# Sequei_board1.net
KiCad netlist of a schematic drawn in EAGLE
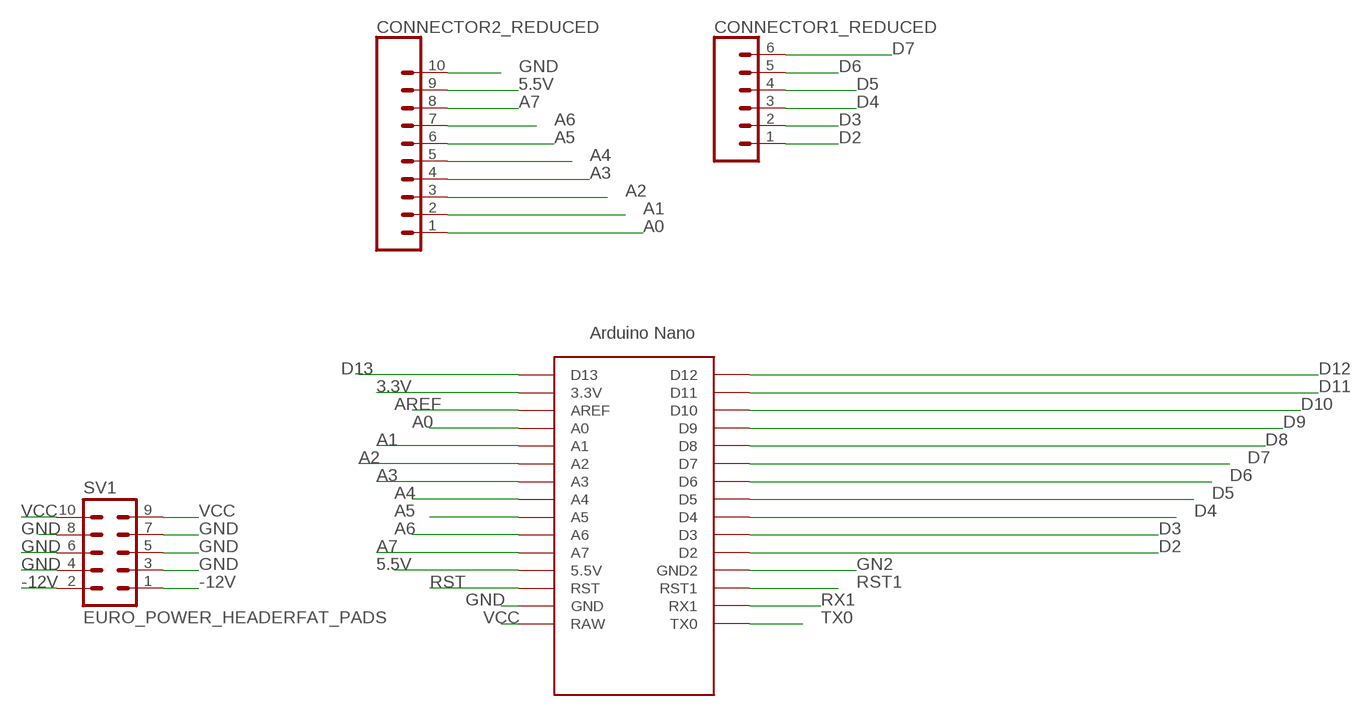
[diagram p0: schematic, sheet 1]

(export (version "E")
  (design (tool "Eeschema 10.0.6"))
  (components
    (comp (ref "CONNECTOR1_REDUCED")
      (value "CONN_06LONGPADS")
      (footprint "eagle-import:1X06_LONGPADS")
      (libsource (lib "eagle-import") (part "CONN_06LONGPADS"))
    )
    (comp (ref "CONNECTOR2_REDUCED")
      (value "CONN_10_LONGPADS10_LONGPADS")
      (footprint "eagle-import:1X10_LONGPADS")
      (libsource (lib "eagle-import") (part "CONN_10_LONGPADS10_LONGPADS"))
    )
    (comp (ref "SV1")
      (value "EURO_POWER_HEADERFAT_PADS")
      (footprint "eagle-import:EURO_PWR_HEADER_FAT")
      (libsource (lib "eagle-import") (part "EURO_POWER_HEADERFAT_PADS"))
    )
    (comp (ref "U$1")
      (value "NANO")
      (footprint "eagle-import:NANO")
      (libsource (lib "eagle-import") (part "NANO"))
    )
  )
  (nets
    (net (code "1") (name "/-12V") (class "Default")
      (node (ref "SV1") (pin "1") (pinfunction "1_1") (pintype "passive"))
      (node (ref "SV1") (pin "2") (pinfunction "2_2") (pintype "passive"))
    )
    (net (code "2") (name "/3.3V") (class "Default")
      (node (ref "U$1") (pin "3.3V") (pinfunction "3.3V_3.3V") (pintype "bidirectional"))
    )
    (net (code "3") (name "/5.5V") (class "Default")
      (node (ref "CONNECTOR2_REDUCED") (pin "9") (pinfunction "9_9") (pintype "passive"))
      (node (ref "U$1") (pin "5V") (pinfunction "5.5V_5V") (pintype "bidirectional"))
    )
    (net (code "4") (name "/A0") (class "Default")
      (node (ref "CONNECTOR2_REDUCED") (pin "1") (pinfunction "1_1") (pintype "passive"))
      (node (ref "U$1") (pin "A0") (pinfunction "A0_A0") (pintype "bidirectional"))
    )
    (net (code "5") (name "/A1") (class "Default")
      (node (ref "CONNECTOR2_REDUCED") (pin "2") (pinfunction "2_2") (pintype "passive"))
      (node (ref "U$1") (pin "A1") (pinfunction "A1_A1") (pintype "bidirectional"))
    )
    (net (code "6") (name "/A2") (class "Default")
      (node (ref "CONNECTOR2_REDUCED") (pin "3") (pinfunction "3_3") (pintype "passive"))
      (node (ref "U$1") (pin "A2") (pinfunction "A2_A2") (pintype "bidirectional"))
    )
    (net (code "7") (name "/A3") (class "Default")
      (node (ref "CONNECTOR2_REDUCED") (pin "4") (pinfunction "4_4") (pintype "passive"))
      (node (ref "U$1") (pin "A3") (pinfunction "A3_A3") (pintype "bidirectional"))
    )
    (net (code "8") (name "/A4") (class "Default")
      (node (ref "CONNECTOR2_REDUCED") (pin "5") (pinfunction "5_5") (pintype "passive"))
      (node (ref "U$1") (pin "A4") (pinfunction "A4_A4") (pintype "bidirectional"))
    )
    (net (code "9") (name "/A5") (class "Default")
      (node (ref "CONNECTOR2_REDUCED") (pin "6") (pinfunction "6_6") (pintype "passive"))
      (node (ref "U$1") (pin "A5") (pinfunction "A5_A5") (pintype "bidirectional"))
    )
    (net (code "10") (name "/A6") (class "Default")
      (node (ref "CONNECTOR2_REDUCED") (pin "7") (pinfunction "7_7") (pintype "passive"))
      (node (ref "U$1") (pin "A6") (pinfunction "A6_A6") (pintype "bidirectional"))
    )
    (net (code "11") (name "/A7") (class "Default")
      (node (ref "CONNECTOR2_REDUCED") (pin "8") (pinfunction "8_8") (pintype "passive"))
      (node (ref "U$1") (pin "A7") (pinfunction "A7_A7") (pintype "bidirectional"))
    )
    (net (code "12") (name "/AREF") (class "Default")
      (node (ref "U$1") (pin "AREF") (pinfunction "AREF_AREF") (pintype "bidirectional"))
    )
    (net (code "13") (name "/D2") (class "Default")
      (node (ref "CONNECTOR1_REDUCED") (pin "1") (pinfunction "1_1") (pintype "passive"))
      (node (ref "U$1") (pin "D2") (pinfunction "D2_D2") (pintype "bidirectional"))
    )
    (net (code "14") (name "/D3") (class "Default")
      (node (ref "CONNECTOR1_REDUCED") (pin "2") (pinfunction "2_2") (pintype "passive"))
      (node (ref "U$1") (pin "D3") (pinfunction "D3_D3") (pintype "bidirectional"))
    )
    (net (code "15") (name "/D4") (class "Default")
      (node (ref "CONNECTOR1_REDUCED") (pin "3") (pinfunction "3_3") (pintype "passive"))
      (node (ref "U$1") (pin "D4") (pinfunction "D4_D4") (pintype "bidirectional"))
    )
    (net (code "16") (name "/D5") (class "Default")
      (node (ref "CONNECTOR1_REDUCED") (pin "4") (pinfunction "4_4") (pintype "passive"))
      (node (ref "U$1") (pin "D5") (pinfunction "D5_D5") (pintype "bidirectional"))
    )
    (net (code "17") (name "/D6") (class "Default")
      (node (ref "CONNECTOR1_REDUCED") (pin "5") (pinfunction "5_5") (pintype "passive"))
      (node (ref "U$1") (pin "D6") (pinfunction "D6_D6") (pintype "bidirectional"))
    )
    (net (code "18") (name "/D7") (class "Default")
      (node (ref "CONNECTOR1_REDUCED") (pin "6") (pinfunction "6_6") (pintype "passive"))
      (node (ref "U$1") (pin "D7") (pinfunction "D7_D7") (pintype "bidirectional"))
    )
    (net (code "19") (name "/D8") (class "Default")
      (node (ref "U$1") (pin "D8") (pinfunction "D8_D8") (pintype "bidirectional"))
    )
    (net (code "20") (name "/D9") (class "Default")
      (node (ref "U$1") (pin "D9") (pinfunction "D9_D9") (pintype "bidirectional"))
    )
    (net (code "21") (name "/D10") (class "Default")
      (node (ref "U$1") (pin "D10") (pinfunction "D10_D10") (pintype "bidirectional"))
    )
    (net (code "22") (name "/D11") (class "Default")
      (node (ref "U$1") (pin "D11") (pinfunction "D11_D11") (pintype "bidirectional"))
    )
    (net (code "23") (name "/D12") (class "Default")
      (node (ref "U$1") (pin "D12") (pinfunction "D12_D12") (pintype "bidirectional"))
    )
    (net (code "24") (name "/D13") (class "Default")
      (node (ref "U$1") (pin "D13") (pinfunction "D13_D13") (pintype "bidirectional"))
    )
    (net (code "25") (name "/GN2") (class "Default")
      (node (ref "U$1") (pin "GND1") (pinfunction "GND2_GND1") (pintype "bidirectional"))
    )
    (net (code "26") (name "/GND") (class "Default")
      (node (ref "CONNECTOR2_REDUCED") (pin "10") (pinfunction "10_10") (pintype "passive"))
      (node (ref "SV1") (pin "3") (pinfunction "3_3") (pintype "passive"))
      (node (ref "SV1") (pin "4") (pinfunction "4_4") (pintype "passive"))
      (node (ref "SV1") (pin "5") (pinfunction "5_5") (pintype "passive"))
      (node (ref "SV1") (pin "6") (pinfunction "6_6") (pintype "passive"))
      (node (ref "SV1") (pin "7") (pinfunction "7_7") (pintype "passive"))
      (node (ref "SV1") (pin "8") (pinfunction "8_8") (pintype "passive"))
      (node (ref "U$1") (pin "GND") (pinfunction "GND_GND") (pintype "bidirectional"))
    )
    (net (code "27") (name "/RST") (class "Default")
      (node (ref "U$1") (pin "RST") (pinfunction "RST_RST") (pintype "bidirectional"))
    )
    (net (code "28") (name "/RST1") (class "Default")
      (node (ref "U$1") (pin "RST1") (pinfunction "RST1_RST1") (pintype "bidirectional"))
    )
    (net (code "29") (name "/RX1") (class "Default")
      (node (ref "U$1") (pin "RX1") (pinfunction "RX1_RX1") (pintype "bidirectional"))
    )
    (net (code "30") (name "/TX0") (class "Default")
      (node (ref "U$1") (pin "TX0") (pinfunction "TX0_TX0") (pintype "bidirectional"))
    )
    (net (code "31") (name "/VCC") (class "Default")
      (node (ref "SV1") (pin "10") (pinfunction "10_10") (pintype "passive"))
      (node (ref "SV1") (pin "9") (pinfunction "9_9") (pintype "passive"))
      (node (ref "U$1") (pin "RAW") (pinfunction "RAW_RAW") (pintype "bidirectional"))
    )
  )
)
